# coursedesign.net
KiCad netlist of a schematic drawn in Altium Designer
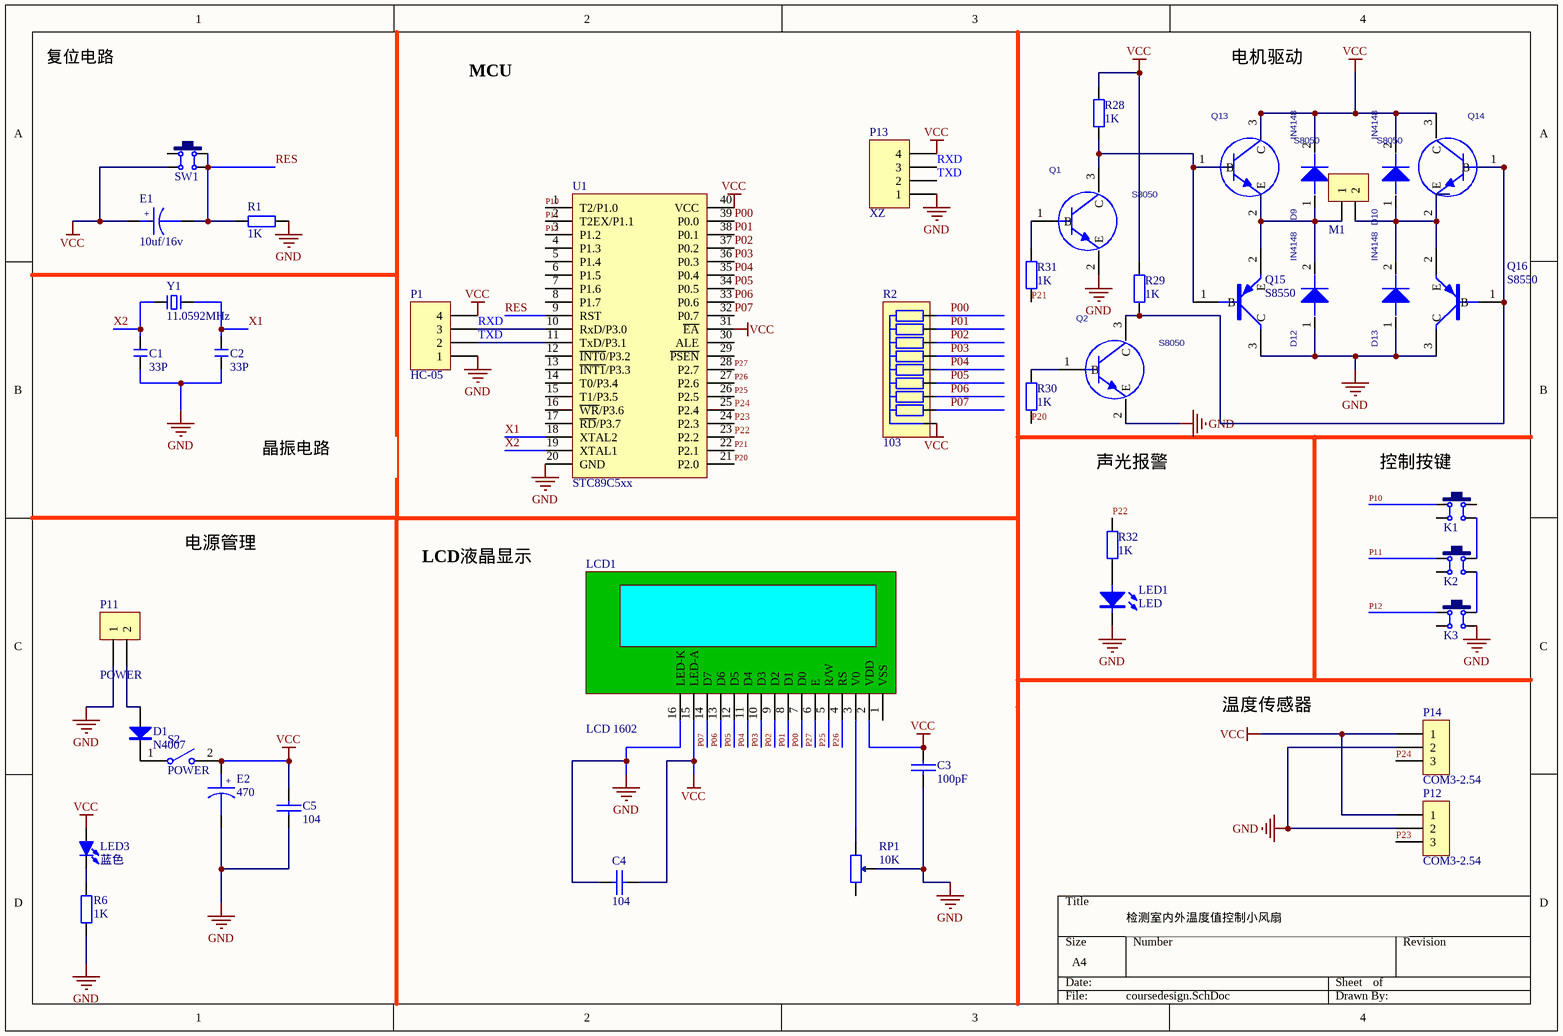
[diagram p0: coursedesign.SchDoc]

(export (version "E")
  (design (tool "Eeschema 10.0.6"))
  (components
    (comp (ref "C1")
      (value "33P")
      (footprint "CC 1.8*3.6")
      (description "直插瓷片电容")
      (fields (field (name "版权归属") "源创客"))
      (libsource (lib "3.1   - 电阻-电容-电感") (part "C-CC"))
    )
    (comp (ref "C2")
      (value "33P")
      (footprint "CC 1.8*3.6")
      (description "直插瓷片电容")
      (fields (field (name "版权归属") "源创客"))
      (libsource (lib "3.1   - 电阻-电容-电感") (part "C-CC"))
    )
    (comp (ref "C3")
      (value "100pF")
      (footprint "RAD0.1")
      (description "Capacitor")
      (libsource (lib "元件库") (part "普通电容"))
    )
    (comp (ref "C4")
      (value "104")
      (footprint "RAD0.1")
      (description "Capacitor")
      (libsource (lib "元件库") (part "普通电容"))
    )
    (comp (ref "C5")
      (value "104")
      (footprint "RAD0.1")
      (description "Capacitor")
      (libsource (lib "元件库") (part "普通电容"))
    )
    (comp (ref "D1")
      (value "N4007")
      (footprint "DO-41")
      (description "整流二极管")
      (fields (field (name "版权归属") "源创客"))
      (libsource (lib "8.1   - 二极管-整流桥") (part "1N4007"))
    )
    (comp (ref "D9")
      (value "IN4148")
      (footprint "DIODE_SOP")
      (libsource (lib "XJDYJB-v1.20") (part "IN4148"))
    )
    (comp (ref "D10")
      (value "IN4148")
      (footprint "DIODE_SOP")
      (libsource (lib "XJDYJB-v1.20") (part "IN4148"))
    )
    (comp (ref "D12")
      (value "IN4148")
      (footprint "DIODE_SOP")
      (libsource (lib "XJDYJB-v1.20") (part "IN4148"))
    )
    (comp (ref "D13")
      (value "IN4148")
      (footprint "DIODE_SOP")
      (libsource (lib "XJDYJB-v1.20") (part "IN4148"))
    )
    (comp (ref "E1")
      (value "10uf/16v")
      (footprint "CAP_2")
      (description "Capacitor")
      (libsource (lib "元件库") (part "电解电容"))
    )
    (comp (ref "E2")
      (value "470")
      (footprint "CAP_2")
      (description "Capacitor")
      (libsource (lib "元件库") (part "电解电容"))
    )
    (comp (ref "K1")
      (value "6x6x5")
      (footprint "TSW DIP-6*6*6")
      (description "直插6x6轻触开关")
      (fields (field (name "版权归属") "源创客"))
      (libsource (lib "5.1   - 按键-开关") (part "TSW DIP-6x6"))
    )
    (comp (ref "K2")
      (value "6x6x5")
      (footprint "TSW DIP-6*6*6")
      (description "直插6x6轻触开关")
      (fields (field (name "版权归属") "源创客"))
      (libsource (lib "5.1   - 按键-开关") (part "TSW DIP-6x6"))
    )
    (comp (ref "K3")
      (value "6x6x5")
      (footprint "TSW DIP-6*6*6")
      (description "直插6x6轻触开关")
      (fields (field (name "版权归属") "源创客"))
      (libsource (lib "5.1   - 按键-开关") (part "TSW DIP-6x6"))
    )
    (comp (ref "LCD1")
      (value "LCD 1602")
      (footprint "LCD-1602")
      (fields (field (name "版权归属") "源创客"))
      (libsource (lib "9.2   - 显示器件") (part "LCD 1602"))
    )
    (comp (ref "LED1") (value "LED") (footprint "LED-D5") (libsource (lib "General") (part "LED")))
    (comp (ref "LED3")
      (value "蓝色")
      (footprint "LED 5MM-G")
      (description "5mm插件LED")
      (fields (field (name "版权归属") "源创客"))
      (libsource (lib "9.1   - LED") (part "LED-5MM"))
    )
    (comp (ref "M1")
      (value "HDR-1X2")
      (footprint "HDR2.54-LI-2P")
      (description "2P接插件")
      (fields (field (name "版权归属") "源创客"))
      (libsource (lib "NE555呼吸灯") (part "Header 2"))
    )
    (comp (ref "P1")
      (value "HC-05")
      (footprint "HDR1X4")
      (description "Header, 4-Pin")
      (fields (field (name "PUBLISHER") "Altium Limited"))
      (libsource (lib "Miscellaneous Connectors") (part "Header 4"))
    )
    (comp (ref "P11")
      (value "POWER")
      (footprint "COM2-2.54")
      (libsource (lib "XJDYJB-v1.20") (part "COM2-2.54"))
    )
    (comp (ref "P12")
      (value "COM3-2.54")
      (footprint "COM3-2.54")
      (libsource (lib "XJDYJB-v1.20") (part "COM3-2.54"))
    )
    (comp (ref "P13")
      (value "XZ")
      (footprint "HDR1X4")
      (description "Header, 4-Pin")
      (fields (field (name "PUBLISHER") "Altium Limited"))
      (libsource (lib "Miscellaneous Connectors") (part "Header 4"))
    )
    (comp (ref "P14")
      (value "COM3-2.54")
      (footprint "COM3-2.54")
      (libsource (lib "XJDYJB-v1.20") (part "COM3-2.54"))
    )
    (comp (ref "Q1")
      (value "S8050")
      (footprint "TO-92")
      (description "NPN")
      (libsource (lib "XJDYJB-v1.20") (part "S8050"))
    )
    (comp (ref "Q2")
      (value "S8050")
      (footprint "TO-92")
      (description "NPN")
      (libsource (lib "XJDYJB-v1.20") (part "S8050"))
    )
    (comp (ref "Q13")
      (value "S8050")
      (footprint "TO-92")
      (description "NPN")
      (libsource (lib "XJDYJB-v1.20") (part "S8050"))
    )
    (comp (ref "Q14")
      (value "S8050")
      (footprint "TO-92")
      (description "NPN")
      (libsource (lib "XJDYJB-v1.20") (part "S8050"))
    )
    (comp (ref "Q15")
      (value "S8550")
      (footprint "TO-92")
      (description "PNP")
      (libsource (lib "XJDYJB-v1.20") (part "S8550"))
    )
    (comp (ref "Q16")
      (value "S8550")
      (footprint "TO-92")
      (description "PNP")
      (libsource (lib "XJDYJB-v1.20") (part "S8550"))
    )
    (comp (ref "R1")
      (value "1K")
      (footprint "RS 1/4W")
      (description "直插色环电阻")
      (fields (field (name "版权归属") "源创客"))
      (libsource (lib "3.1   - 电阻-电容-电感") (part "R-CRR"))
    )
    (comp (ref "R2")
      (value "103")
      (footprint "R SIP9-2.54")
      (description "单列直插排阻")
      (fields (field (name "版权归属") "源创客"))
      (libsource (lib "3.1   - 电阻-电容-电感") (part "R SIP9"))
    )
    (comp (ref "R6")
      (value "1K")
      (footprint "RS 1/4W")
      (description "直插色环电阻")
      (fields (field (name "版权归属") "源创客"))
      (libsource (lib "3.1   - 电阻-电容-电感") (part "R-CRR"))
    )
    (comp (ref "R28")
      (value "1K")
      (footprint "RES-0.25W-6.5X2.5-10.16-0.6")
      (description "Resistor")
      (libsource (lib "General") (part "RES"))
    )
    (comp (ref "R29")
      (value "1K")
      (footprint "RES-0.25W-6.5X2.5-10.16-0.6")
      (description "Resistor")
      (libsource (lib "General") (part "RES"))
    )
    (comp (ref "R30")
      (value "1K")
      (footprint "RES-0.25W-6.5X2.5-10.16-0.6")
      (description "Resistor")
      (libsource (lib "General") (part "RES"))
    )
    (comp (ref "R31")
      (value "1K")
      (footprint "RES-0.25W-6.5X2.5-10.16-0.6")
      (description "Resistor")
      (libsource (lib "General") (part "RES"))
    )
    (comp (ref "R32")
      (value "1K")
      (footprint "RES-0.25W-6.5X2.5-10.16-0.6")
      (description "Resistor")
      (libsource (lib "General") (part "RES"))
    )
    (comp (ref "RP1")
      (value "10K")
      (footprint "3296W")
      (description "插件单联电位器")
      (fields (field (name "版权归属") "源创客"))
      (libsource (lib "3.1   - 电阻-电容-电感") (part "RP-ID"))
    )
    (comp (ref "S2")
      (value "POWER")
      (footprint "KCD1-101")
      (description "1路单刀船型开关")
      (fields (field (name "版权归属") "源创客"))
      (libsource (lib "5.1   - 按键-开关") (part "KCD1-101"))
    )
    (comp (ref "SW1")
      (value "6x6x5")
      (footprint "TSW DIP-6*6*6")
      (description "直插6x6轻触开关")
      (fields (field (name "版权归属") "源创客"))
      (libsource (lib "5.1   - 按键-开关") (part "TSW DIP-6x6"))
    )
    (comp (ref "U1")
      (value "STC89C5xx")
      (footprint "DIP40-600")
      (description "STC单片机")
      (fields (field (name "版权归属") "源创客"))
      (libsource (lib "2.3   - STC系列单片机") (part "STC89C5xx"))
    )
    (comp (ref "Y1")
      (value "11.0592MHz")
      (footprint "OSC HC-49S")
      (description "2脚无源脚晶振")
      (fields (field (name "版权归属") "源创客"))
      (libsource (lib "10.1 - 保险丝-晶振") (part "XTAL-2P"))
    )
  )
  (nets
    (net (code "1") (name "/P00") (class "Default")
      (node (ref "LCD1") (pin "7") (pinfunction "D0_7") (pintype "passive"))
      (node (ref "R2") (pin "9") (pinfunction "9_9") (pintype "passive"))
      (node (ref "U1") (pin "39") (pinfunction "P0.0_39") (pintype "passive"))
    )
    (net (code "2") (name "/P01") (class "Default")
      (node (ref "LCD1") (pin "8") (pinfunction "D1_8") (pintype "passive"))
      (node (ref "R2") (pin "8") (pinfunction "8_8") (pintype "passive"))
      (node (ref "U1") (pin "38") (pinfunction "P0.1_38") (pintype "passive"))
    )
    (net (code "3") (name "/P02") (class "Default")
      (node (ref "LCD1") (pin "9") (pinfunction "D2_9") (pintype "passive"))
      (node (ref "R2") (pin "7") (pinfunction "7_7") (pintype "passive"))
      (node (ref "U1") (pin "37") (pinfunction "P0.2_37") (pintype "passive"))
    )
    (net (code "4") (name "/P03") (class "Default")
      (node (ref "LCD1") (pin "10") (pinfunction "D3_10") (pintype "passive"))
      (node (ref "R2") (pin "6") (pinfunction "6_6") (pintype "passive"))
      (node (ref "U1") (pin "36") (pinfunction "P0.3_36") (pintype "passive"))
    )
    (net (code "5") (name "/P04") (class "Default")
      (node (ref "LCD1") (pin "11") (pinfunction "D4_11") (pintype "passive"))
      (node (ref "R2") (pin "5") (pinfunction "5_5") (pintype "passive"))
      (node (ref "U1") (pin "35") (pinfunction "P0.4_35") (pintype "passive"))
    )
    (net (code "6") (name "/P05") (class "Default")
      (node (ref "LCD1") (pin "12") (pinfunction "D5_12") (pintype "passive"))
      (node (ref "R2") (pin "4") (pinfunction "4_4") (pintype "passive"))
      (node (ref "U1") (pin "34") (pinfunction "P0.5_34") (pintype "passive"))
    )
    (net (code "7") (name "/P06") (class "Default")
      (node (ref "LCD1") (pin "13") (pinfunction "D6_13") (pintype "passive"))
      (node (ref "R2") (pin "3") (pinfunction "3_3") (pintype "passive"))
      (node (ref "U1") (pin "33") (pinfunction "P0.6_33") (pintype "passive"))
    )
    (net (code "8") (name "/P07") (class "Default")
      (node (ref "LCD1") (pin "14") (pinfunction "D7_14") (pintype "passive"))
      (node (ref "R2") (pin "2") (pinfunction "2_2") (pintype "passive"))
      (node (ref "U1") (pin "32") (pinfunction "P0.7_32") (pintype "passive"))
    )
    (net (code "9") (name "/P10") (class "Default")
      (node (ref "K1") (pin "1") (pinfunction "1_1") (pintype "passive"))
      (node (ref "U1") (pin "1") (pinfunction "T2/P1.0_1") (pintype "passive"))
    )
    (net (code "10") (name "/P11") (class "Default")
      (node (ref "K2") (pin "1") (pinfunction "1_1") (pintype "passive"))
      (node (ref "U1") (pin "2") (pinfunction "T2EX/P1.1_2") (pintype "passive"))
    )
    (net (code "11") (name "/P12") (class "Default")
      (node (ref "K3") (pin "1") (pinfunction "1_1") (pintype "passive"))
      (node (ref "U1") (pin "3") (pinfunction "P1.2_3") (pintype "passive"))
    )
    (net (code "12") (name "/P20") (class "Default")
      (node (ref "R30") (pin "1") (pinfunction "1_1") (pintype "passive"))
      (node (ref "U1") (pin "21") (pinfunction "P2.0_21") (pintype "passive"))
    )
    (net (code "13") (name "/P21") (class "Default")
      (node (ref "R31") (pin "1") (pinfunction "1_1") (pintype "passive"))
      (node (ref "U1") (pin "22") (pinfunction "P2.1_22") (pintype "passive"))
    )
    (net (code "14") (name "/P22") (class "Default")
      (node (ref "R32") (pin "2") (pinfunction "2_2") (pintype "passive"))
      (node (ref "U1") (pin "23") (pinfunction "P2.2_23") (pintype "passive"))
    )
    (net (code "15") (name "/P23") (class "Default")
      (node (ref "P12") (pin "3") (pinfunction "3_3") (pintype "passive"))
      (node (ref "U1") (pin "24") (pinfunction "P2.3_24") (pintype "passive"))
    )
    (net (code "16") (name "/P24") (class "Default")
      (node (ref "P14") (pin "3") (pinfunction "3_3") (pintype "passive"))
      (node (ref "U1") (pin "25") (pinfunction "P2.4_25") (pintype "passive"))
    )
    (net (code "17") (name "/P25") (class "Default")
      (node (ref "LCD1") (pin "5") (pinfunction "R/W_5") (pintype "passive"))
      (node (ref "U1") (pin "26") (pinfunction "P2.5_26") (pintype "passive"))
    )
    (net (code "18") (name "/P26") (class "Default")
      (node (ref "LCD1") (pin "4") (pinfunction "RS_4") (pintype "passive"))
      (node (ref "U1") (pin "27") (pinfunction "P2.6_27") (pintype "passive"))
    )
    (net (code "19") (name "/P27") (class "Default")
      (node (ref "LCD1") (pin "6") (pinfunction "E_6") (pintype "passive"))
      (node (ref "U1") (pin "28") (pinfunction "P2.7_28") (pintype "passive"))
    )
    (net (code "20") (name "/RES") (class "Default")
      (node (ref "E1") (pin "2") (pinfunction "2_2") (pintype "passive"))
      (node (ref "R1") (pin "1") (pinfunction "1_1") (pintype "passive"))
      (node (ref "SW1") (pin "2") (pinfunction "2_2") (pintype "passive"))
      (node (ref "SW1") (pin "3") (pinfunction "3_3") (pintype "passive"))
      (node (ref "U1") (pin "9") (pinfunction "RST_9") (pintype "passive"))
    )
    (net (code "21") (name "/RXD") (class "Default")
      (node (ref "P1") (pin "3") (pinfunction "3_3") (pintype "passive"))
      (node (ref "P13") (pin "3") (pinfunction "3_3") (pintype "passive"))
      (node (ref "U1") (pin "10") (pinfunction "RxD/P3.0_10") (pintype "passive"))
    )
    (net (code "22") (name "/TXD") (class "Default")
      (node (ref "P1") (pin "2") (pinfunction "2_2") (pintype "passive"))
      (node (ref "P13") (pin "2") (pinfunction "2_2") (pintype "passive"))
      (node (ref "U1") (pin "11") (pinfunction "TxD/P3.1_11") (pintype "passive"))
    )
    (net (code "23") (name "/X1") (class "Default")
      (node (ref "C2") (pin "1") (pinfunction "1_1") (pintype "passive"))
      (node (ref "U1") (pin "18") (pinfunction "XTAL2_18") (pintype "passive"))
      (node (ref "Y1") (pin "2") (pinfunction "2_2") (pintype "passive"))
    )
    (net (code "24") (name "/X2") (class "Default")
      (node (ref "C1") (pin "1") (pinfunction "1_1") (pintype "passive"))
      (node (ref "U1") (pin "19") (pinfunction "XTAL1_19") (pintype "passive"))
      (node (ref "Y1") (pin "1") (pinfunction "1_1") (pintype "passive"))
    )
    (net (code "25") (name "GND") (class "Default")
      (node (ref "C1") (pin "2") (pinfunction "2_2") (pintype "passive"))
      (node (ref "C2") (pin "2") (pinfunction "2_2") (pintype "passive"))
      (node (ref "C3") (pin "1") (pinfunction "1_1") (pintype "passive"))
      (node (ref "C4") (pin "1") (pinfunction "1_1") (pintype "passive"))
      (node (ref "C5") (pin "2") (pinfunction "2_2") (pintype "passive"))
      (node (ref "D12") (pin "1") (pinfunction "+_1") (pintype "passive"))
      (node (ref "D13") (pin "1") (pinfunction "+_1") (pintype "passive"))
      (node (ref "E2") (pin "2") (pinfunction "2_2") (pintype "passive"))
      (node (ref "K3") (pin "3") (pinfunction "3_3") (pintype "passive"))
      (node (ref "LCD1") (pin "16") (pinfunction "LED-K_16") (pintype "passive"))
      (node (ref "LED1") (pin "2") (pinfunction "C_2") (pintype "passive"))
      (node (ref "P1") (pin "1") (pinfunction "1_1") (pintype "passive"))
      (node (ref "P11") (pin "1") (pinfunction "1_1") (pintype "passive"))
      (node (ref "P12") (pin "2") (pinfunction "2_2") (pintype "passive"))
      (node (ref "P13") (pin "1") (pinfunction "1_1") (pintype "passive"))
      (node (ref "P14") (pin "2") (pinfunction "2_2") (pintype "passive"))
      (node (ref "Q1") (pin "2") (pinfunction "E_2") (pintype "passive"))
      (node (ref "Q15") (pin "3") (pinfunction "C_3") (pintype "passive"))
      (node (ref "Q16") (pin "3") (pinfunction "C_3") (pintype "passive"))
      (node (ref "Q2") (pin "2") (pinfunction "E_2") (pintype "passive"))
      (node (ref "R1") (pin "2") (pinfunction "2_2") (pintype "passive"))
      (node (ref "R6") (pin "1") (pinfunction "1_1") (pintype "passive"))
      (node (ref "RP1") (pin "2") (pinfunction "2_2") (pintype "passive"))
      (node (ref "U1") (pin "20") (pinfunction "GND_20") (pintype "passive"))
    )
    (net (code "26") (name "Net-(D1-A)") (class "Default")
      (node (ref "D1") (pin "1") (pinfunction "A_1") (pintype "passive"))
      (node (ref "P11") (pin "2") (pinfunction "2_2") (pintype "passive"))
    )
    (net (code "27") (name "Net-(D1-K)") (class "Default")
      (node (ref "D1") (pin "2") (pinfunction "K_2") (pintype "passive"))
      (node (ref "S2") (pin "1") (pinfunction "1_1") (pintype "passive"))
    )
    (net (code "28") (name "Net-(D10-+)") (class "Default")
      (node (ref "D10") (pin "1") (pinfunction "+_1") (pintype "passive"))
      (node (ref "D13") (pin "2") (pinfunction "-_2") (pintype "passive"))
      (node (ref "M1") (pin "2") (pinfunction "2_2") (pintype "passive"))
      (node (ref "Q14") (pin "2") (pinfunction "E_2") (pintype "passive"))
      (node (ref "Q16") (pin "2") (pinfunction "E_2") (pintype "passive"))
    )
    (net (code "29") (name "Net-(D12--)") (class "Default")
      (node (ref "D12") (pin "2") (pinfunction "-_2") (pintype "passive"))
      (node (ref "D9") (pin "1") (pinfunction "+_1") (pintype "passive"))
      (node (ref "M1") (pin "1") (pinfunction "1_1") (pintype "passive"))
      (node (ref "Q13") (pin "2") (pinfunction "E_2") (pintype "passive"))
      (node (ref "Q15") (pin "2") (pinfunction "E_2") (pintype "passive"))
    )
    (net (code "30") (name "Net-(K1-Pad3)") (class "Default")
      (node (ref "K1") (pin "3") (pinfunction "3_3") (pintype "passive"))
      (node (ref "K2") (pin "2") (pinfunction "2_2") (pintype "passive"))
    )
    (net (code "31") (name "Net-(K2-Pad3)") (class "Default")
      (node (ref "K2") (pin "3") (pinfunction "3_3") (pintype "passive"))
      (node (ref "K3") (pin "2") (pinfunction "2_2") (pintype "passive"))
    )
    (net (code "32") (name "Net-(LCD1-V0)") (class "Default")
      (node (ref "LCD1") (pin "3") (pinfunction "V0_3") (pintype "passive"))
      (node (ref "RP1") (pin "1") (pinfunction "1_1") (pintype "passive"))
    )
    (net (code "33") (name "Net-(LED1-A)") (class "Default")
      (node (ref "LED1") (pin "1") (pinfunction "A_1") (pintype "passive"))
      (node (ref "R32") (pin "1") (pinfunction "1_1") (pintype "passive"))
    )
    (net (code "34") (name "Net-(LED3-K)") (class "Default")
      (node (ref "LED3") (pin "2") (pinfunction "K_2") (pintype "passive"))
      (node (ref "R6") (pin "2") (pinfunction "2_2") (pintype "passive"))
    )
    (net (code "35") (name "Net-(Q1-B)") (class "Default")
      (node (ref "Q1") (pin "1") (pinfunction "B_1") (pintype "passive"))
      (node (ref "R31") (pin "2") (pinfunction "2_2") (pintype "passive"))
    )
    (net (code "36") (name "Net-(Q1-C)") (class "Default")
      (node (ref "Q1") (pin "3") (pinfunction "C_3") (pintype "passive"))
      (node (ref "Q13") (pin "1") (pinfunction "B_1") (pintype "passive"))
      (node (ref "Q15") (pin "1") (pinfunction "B_1") (pintype "passive"))
      (node (ref "R28") (pin "1") (pinfunction "1_1") (pintype "passive"))
    )
    (net (code "37") (name "Net-(Q2-B)") (class "Default")
      (node (ref "Q2") (pin "1") (pinfunction "B_1") (pintype "passive"))
      (node (ref "R30") (pin "2") (pinfunction "2_2") (pintype "passive"))
    )
    (net (code "38") (name "Net-(Q14-B)") (class "Default")
      (node (ref "Q14") (pin "1") (pinfunction "B_1") (pintype "passive"))
      (node (ref "Q16") (pin "1") (pinfunction "B_1") (pintype "passive"))
      (node (ref "Q2") (pin "3") (pinfunction "C_3") (pintype "passive"))
      (node (ref "R29") (pin "1") (pinfunction "1_1") (pintype "passive"))
    )
    (net (code "39") (name "VCC") (class "Default")
      (node (ref "C3") (pin "2") (pinfunction "2_2") (pintype "passive"))
      (node (ref "C4") (pin "2") (pinfunction "2_2") (pintype "passive"))
      (node (ref "C5") (pin "1") (pinfunction "1_1") (pintype "passive"))
      (node (ref "D10") (pin "2") (pinfunction "-_2") (pintype "passive"))
      (node (ref "D9") (pin "2") (pinfunction "-_2") (pintype "passive"))
      (node (ref "E1") (pin "1") (pinfunction "1_1") (pintype "passive"))
      (node (ref "E2") (pin "1") (pinfunction "1_1") (pintype "passive"))
      (node (ref "LCD1") (pin "15") (pinfunction "LED-A_15") (pintype "passive"))
      (node (ref "LCD1") (pin "2") (pinfunction "VDD_2") (pintype "passive"))
      (node (ref "LED3") (pin "1") (pinfunction "A_1") (pintype "passive"))
      (node (ref "P1") (pin "4") (pinfunction "4_4") (pintype "passive"))
      (node (ref "P12") (pin "1") (pinfunction "1_1") (pintype "passive"))
      (node (ref "P13") (pin "4") (pinfunction "4_4") (pintype "passive"))
      (node (ref "P14") (pin "1") (pinfunction "1_1") (pintype "passive"))
      (node (ref "Q13") (pin "3") (pinfunction "C_3") (pintype "passive"))
      (node (ref "Q14") (pin "3") (pinfunction "C_3") (pintype "passive"))
      (node (ref "R2") (pin "1") (pinfunction "1_1") (pintype "passive"))
      (node (ref "R28") (pin "2") (pinfunction "2_2") (pintype "passive"))
      (node (ref "R29") (pin "2") (pinfunction "2_2") (pintype "passive"))
      (node (ref "S2") (pin "2") (pinfunction "2_2") (pintype "passive"))
      (node (ref "SW1") (pin "4") (pinfunction "4_4") (pintype "passive"))
      (node (ref "U1") (pin "31") (pinfunction "~{EA}_31") (pintype "passive"))
      (node (ref "U1") (pin "40") (pinfunction "VCC_40") (pintype "passive"))
    )
    (net (code "40") (name "unconnected-(K1-Pad2)") (class "Default")
      (node (ref "K1") (pin "2") (pinfunction "2_2") (pintype "passive"))
    )
    (net (code "41") (name "unconnected-(K1-Pad4)") (class "Default")
      (node (ref "K1") (pin "4") (pinfunction "4_4") (pintype "passive"))
    )
    (net (code "42") (name "unconnected-(K2-Pad4)") (class "Default")
      (node (ref "K2") (pin "4") (pinfunction "4_4") (pintype "passive"))
    )
    (net (code "43") (name "unconnected-(K3-Pad4)") (class "Default")
      (node (ref "K3") (pin "4") (pinfunction "4_4") (pintype "passive"))
    )
    (net (code "44") (name "unconnected-(LCD1-VSS-Pad1)") (class "Default")
      (node (ref "LCD1") (pin "1") (pinfunction "VSS_1") (pintype "passive"))
    )
    (net (code "45") (name "unconnected-(RP1-Pad3)") (class "Default")
      (node (ref "RP1") (pin "3") (pinfunction "3_3") (pintype "passive"))
    )
    (net (code "46") (name "unconnected-(SW1-Pad1)") (class "Default")
      (node (ref "SW1") (pin "1") (pinfunction "1_1") (pintype "passive"))
    )
    (net (code "47") (name "unconnected-(U1-ALE-Pad30)") (class "Default")
      (node (ref "U1") (pin "30") (pinfunction "ALE_30") (pintype "passive"))
    )
    (net (code "48") (name "unconnected-(U1-P1.3-Pad4)") (class "Default")
      (node (ref "U1") (pin "4") (pinfunction "P1.3_4") (pintype "passive"))
    )
    (net (code "49") (name "unconnected-(U1-P1.4-Pad5)") (class "Default")
      (node (ref "U1") (pin "5") (pinfunction "P1.4_5") (pintype "passive"))
    )
    (net (code "50") (name "unconnected-(U1-P1.5-Pad6)") (class "Default")
      (node (ref "U1") (pin "6") (pinfunction "P1.5_6") (pintype "passive"))
    )
    (net (code "51") (name "unconnected-(U1-P1.6-Pad7)") (class "Default")
      (node (ref "U1") (pin "7") (pinfunction "P1.6_7") (pintype "passive"))
    )
    (net (code "52") (name "unconnected-(U1-P1.7-Pad8)") (class "Default")
      (node (ref "U1") (pin "8") (pinfunction "P1.7_8") (pintype "passive"))
    )
    (net (code "53") (name "unconnected-(U1-T0{slash}P3.4-Pad14)") (class "Default")
      (node (ref "U1") (pin "14") (pinfunction "T0/P3.4_14") (pintype "passive"))
    )
    (net (code "54") (name "unconnected-(U1-T1{slash}P3.5-Pad15)") (class "Default")
      (node (ref "U1") (pin "15") (pinfunction "T1/P3.5_15") (pintype "passive"))
    )
    (net (code "55") (name "unconnected-(U1-~{INT0}{slash}P3.2-Pad12)") (class "Default")
      (node (ref "U1") (pin "12") (pinfunction "~{INT0}/P3.2_12") (pintype "passive"))
    )
    (net (code "56") (name "unconnected-(U1-~{INT1}{slash}P3.3-Pad13)") (class "Default")
      (node (ref "U1") (pin "13") (pinfunction "~{INT1}/P3.3_13") (pintype "passive"))
    )
    (net (code "57") (name "unconnected-(U1-~{PSEN}-Pad29)") (class "Default")
      (node (ref "U1") (pin "29") (pinfunction "~{PSEN}_29") (pintype "passive"))
    )
    (net (code "58") (name "unconnected-(U1-~{RD}{slash}P3.7-Pad17)") (class "Default")
      (node (ref "U1") (pin "17") (pinfunction "~{RD}/P3.7_17") (pintype "passive"))
    )
    (net (code "59") (name "unconnected-(U1-~{WR}{slash}P3.6-Pad16)") (class "Default")
      (node (ref "U1") (pin "16") (pinfunction "~{WR}/P3.6_16") (pintype "passive"))
    )
  )
)
